# wrist.net
KiCad netlist of a schematic drawn in EAGLE
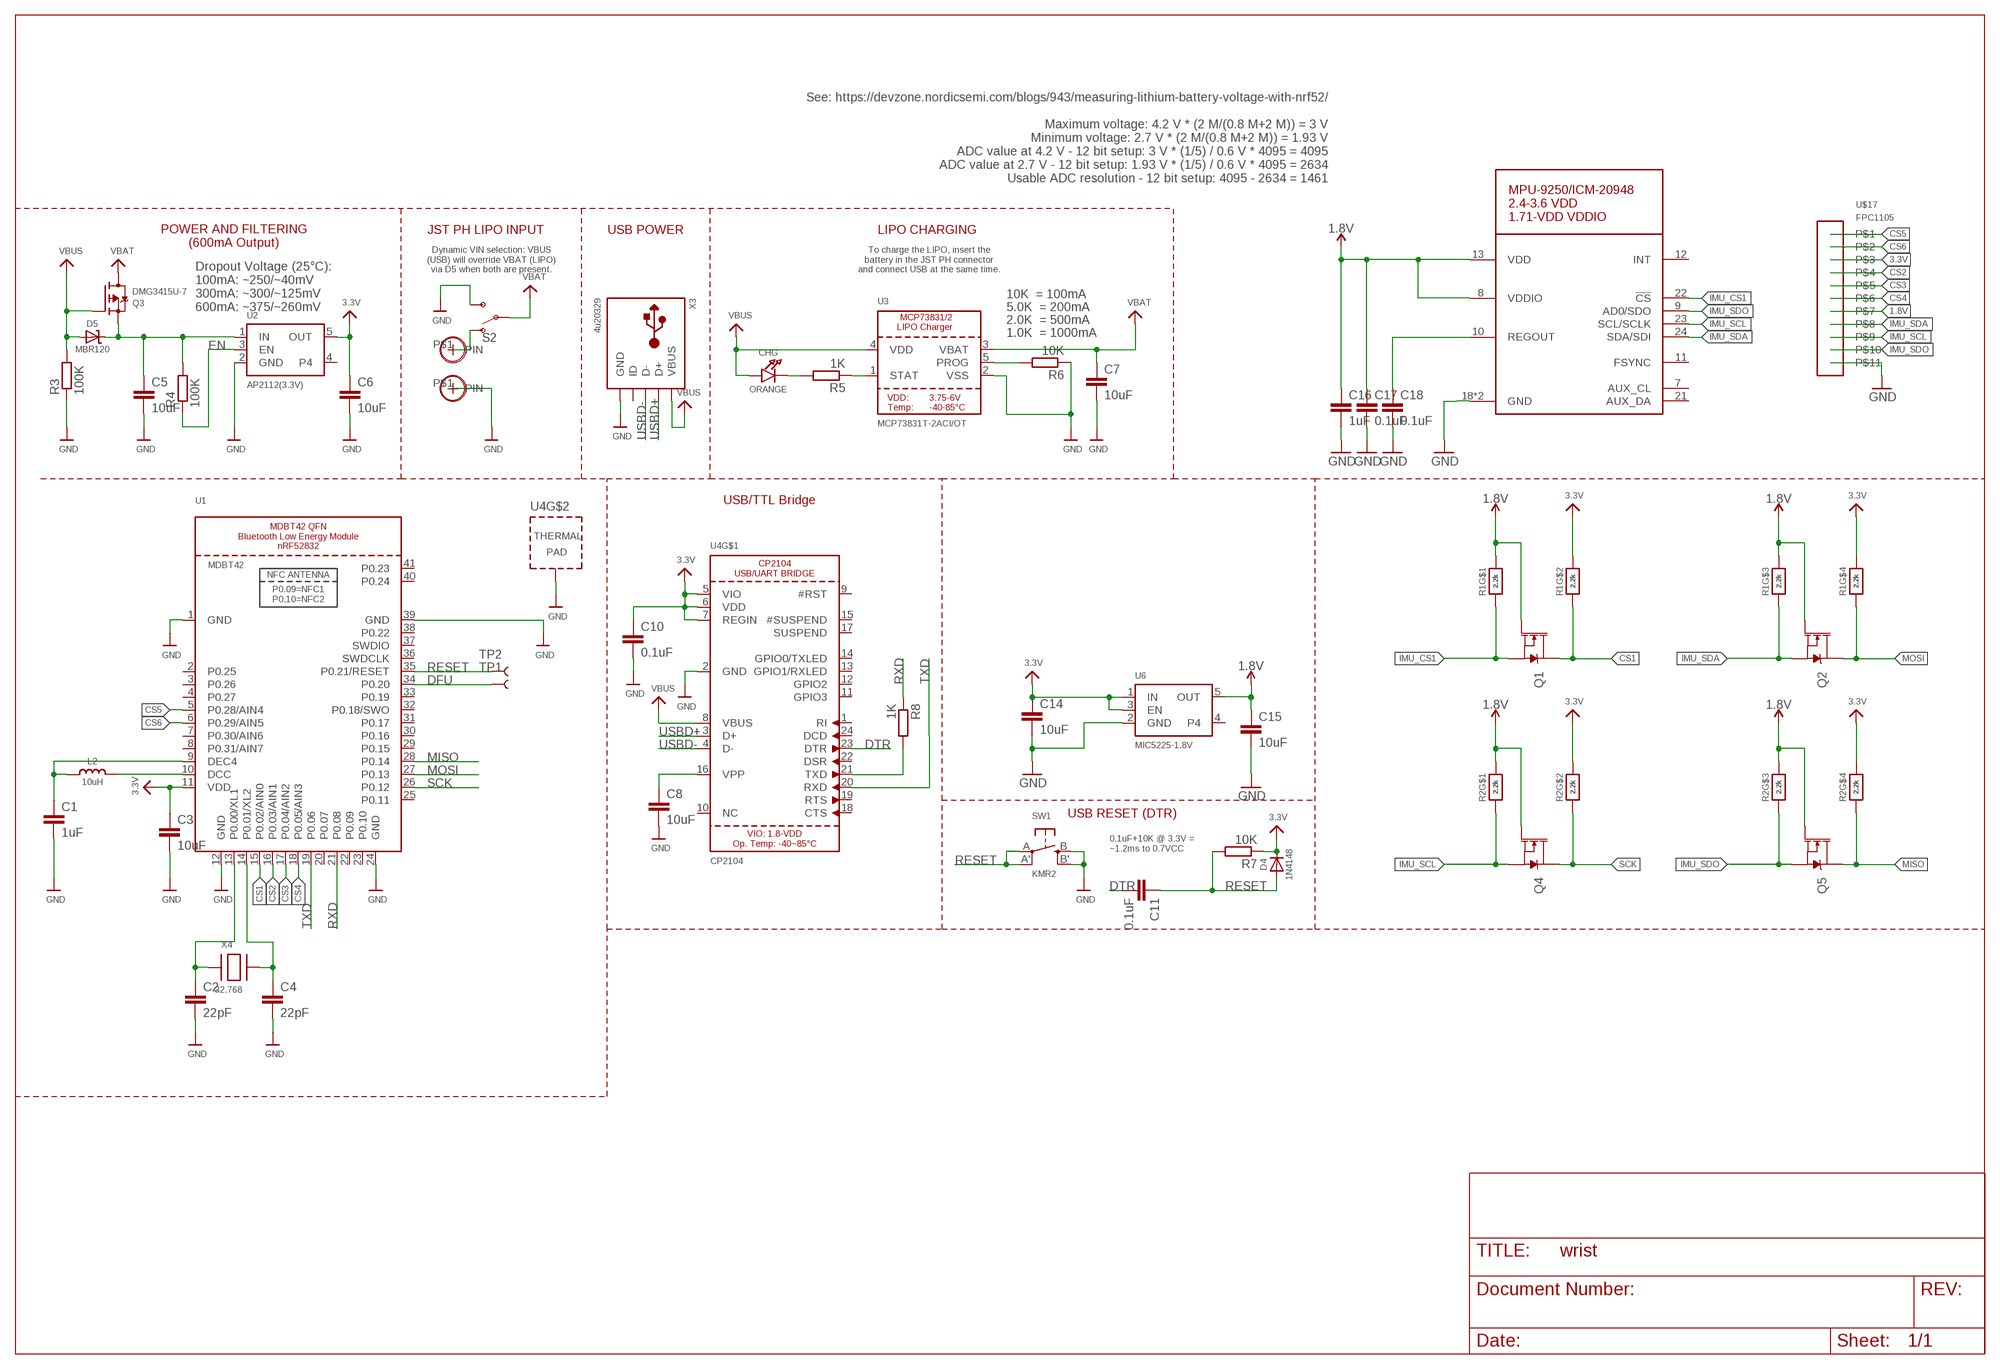
[diagram p0: schematic, sheet 1]

(export (version "E")
  (design (tool "Eeschema 10.0.6"))
  (components
    (comp (ref "C1")
      (value "1uF")
      (footprint "eagle-import:SPARKFUN-CAPACITORS_0402")
      (libsource (lib "eagle-import") (part "SPARKFUN-CAPACITORS_0.1UF-0402-16V-10%"))
    )
    (comp (ref "C2")
      (value "22pF")
      (footprint "eagle-import:SPARKFUN-CAPACITORS_0402")
      (libsource (lib "eagle-import") (part "SPARKFUN-CAPACITORS_0.1UF-0402-16V-10%"))
    )
    (comp (ref "C3")
      (value "10uF")
      (footprint "eagle-import:SPARKFUN-CAPACITORS_0402")
      (libsource (lib "eagle-import") (part "SPARKFUN-CAPACITORS_0.1UF-0402-16V-10%"))
    )
    (comp (ref "C4")
      (value "22pF")
      (footprint "eagle-import:SPARKFUN-CAPACITORS_0402")
      (libsource (lib "eagle-import") (part "SPARKFUN-CAPACITORS_0.1UF-0402-16V-10%"))
    )
    (comp (ref "C5")
      (value "10uF")
      (footprint "eagle-import:SPARKFUN-CAPACITORS_0402")
      (libsource (lib "eagle-import") (part "SPARKFUN-CAPACITORS_0.1UF-0402-16V-10%"))
    )
    (comp (ref "C6")
      (value "10uF")
      (footprint "eagle-import:SPARKFUN-CAPACITORS_0402")
      (libsource (lib "eagle-import") (part "SPARKFUN-CAPACITORS_0.1UF-0402-16V-10%"))
    )
    (comp (ref "C7")
      (value "10uF")
      (footprint "eagle-import:SPARKFUN-CAPACITORS_0402")
      (libsource (lib "eagle-import") (part "SPARKFUN-CAPACITORS_0.1UF-0402-16V-10%"))
    )
    (comp (ref "C8")
      (value "10uF")
      (footprint "eagle-import:SPARKFUN-CAPACITORS_0402")
      (libsource (lib "eagle-import") (part "SPARKFUN-CAPACITORS_0.1UF-0402-16V-10%"))
    )
    (comp (ref "C10")
      (value "0.1uF")
      (footprint "eagle-import:SPARKFUN-CAPACITORS_0402")
      (libsource (lib "eagle-import") (part "SPARKFUN-CAPACITORS_0.1UF-0402-16V-10%"))
    )
    (comp (ref "C11")
      (value "0.1uF")
      (footprint "eagle-import:SPARKFUN-CAPACITORS_0402")
      (libsource (lib "eagle-import") (part "SPARKFUN-CAPACITORS_0.1UF-0402-16V-10%"))
    )
    (comp (ref "C14")
      (value "10uF")
      (footprint "eagle-import:SPARKFUN-CAPACITORS_0402")
      (libsource (lib "eagle-import") (part "SPARKFUN-CAPACITORS_0.1UF-0402-16V-10%"))
    )
    (comp (ref "C15")
      (value "10uF")
      (footprint "eagle-import:SPARKFUN-CAPACITORS_0402")
      (libsource (lib "eagle-import") (part "SPARKFUN-CAPACITORS_0.1UF-0402-16V-10%"))
    )
    (comp (ref "C16")
      (value "1uF")
      (footprint "eagle-import:SPARKFUN-CAPACITORS_0402")
      (libsource (lib "eagle-import") (part "SPARKFUN-CAPACITORS_0.1UF-0402-16V-10%"))
    )
    (comp (ref "C17")
      (value "0.1uF")
      (footprint "eagle-import:SPARKFUN-CAPACITORS_0402")
      (libsource (lib "eagle-import") (part "SPARKFUN-CAPACITORS_0.1UF-0402-16V-10%"))
    )
    (comp (ref "C18")
      (value "0.1uF")
      (footprint "eagle-import:SPARKFUN-CAPACITORS_0402")
      (libsource (lib "eagle-import") (part "SPARKFUN-CAPACITORS_0.1UF-0402-16V-10%"))
    )
    (comp (ref "CHG")
      (value "ORANGE")
      (footprint "eagle-import:CHIPLED_0805_NOOUTLINE")
      (libsource (lib "eagle-import") (part "LED0805_NOOUTLINE"))
    )
    (comp (ref "D4")
      (value "1N4148")
      (footprint "eagle-import:SOD-323")
      (libsource (lib "eagle-import") (part "DIODESOD-323"))
    )
    (comp (ref "D5")
      (value "MBR120")
      (footprint "eagle-import:SOD-123")
      (libsource (lib "eagle-import") (part "DIODE-SCHOTTKYSOD-123"))
    )
    (comp (ref "IC1")
      (value "ADAFRUIT_SENSOR_MPU-9250_ICM20948")
      (footprint "eagle-import:ADAFRUIT_SENSOR_QFN24_3MM_NOEP")
      (libsource (lib "eagle-import") (part "ADAFRUIT_SENSOR_MPU-9250_ICM20948"))
    )
    (comp (ref "L2")
      (value "10uH")
      (footprint "eagle-import:0805-NO")
      (libsource (lib "eagle-import") (part "INDUCTOR0805-NO"))
    )
    (comp (ref "Q1")
      (value "20V/0.2A/8MHz/1.2Ω/1Vth")
      (footprint "eagle-import:SPARKFUN-DISCRETESEMI_SOT-416FL")
      (libsource (lib "eagle-import") (part "SPARKFUN-DISCRETESEMI_MOSFET-NCH-RE1C002UN"))
    )
    (comp (ref "Q2")
      (value "20V/0.2A/8MHz/1.2Ω/1Vth")
      (footprint "eagle-import:SPARKFUN-DISCRETESEMI_SOT-416FL")
      (libsource (lib "eagle-import") (part "SPARKFUN-DISCRETESEMI_MOSFET-NCH-RE1C002UN"))
    )
    (comp (ref "Q3")
      (value "DMG3415U-7")
      (footprint "eagle-import:SOT23-R")
      (libsource (lib "eagle-import") (part "MOSFET-P"))
    )
    (comp (ref "Q4")
      (value "20V/0.2A/8MHz/1.2Ω/1Vth")
      (footprint "eagle-import:SPARKFUN-DISCRETESEMI_SOT-416FL")
      (libsource (lib "eagle-import") (part "SPARKFUN-DISCRETESEMI_MOSFET-NCH-RE1C002UN"))
    )
    (comp (ref "Q5")
      (value "20V/0.2A/8MHz/1.2Ω/1Vth")
      (footprint "eagle-import:SPARKFUN-DISCRETESEMI_SOT-416FL")
      (libsource (lib "eagle-import") (part "SPARKFUN-DISCRETESEMI_MOSFET-NCH-RE1C002UN"))
    )
    (comp (ref "R1")
      (value "2.2k")
      (footprint "eagle-import:MICROBUILDER_RESPACK_4X0603")
      (libsource (lib "eagle-import") (part "MICROBUILDER_RESISTOR_4PACK"))
    )
    (comp (ref "R2")
      (value "2.2k")
      (footprint "eagle-import:MICROBUILDER_RESPACK_4X0603")
      (libsource (lib "eagle-import") (part "MICROBUILDER_RESISTOR_4PACK"))
    )
    (comp (ref "R3")
      (value "100K")
      (footprint "eagle-import:R0603")
      (libsource (lib "eagle-import") (part "R-EU_R0603"))
    )
    (comp (ref "R4")
      (value "100K")
      (footprint "eagle-import:R0603")
      (libsource (lib "eagle-import") (part "R-EU_R0603"))
    )
    (comp (ref "R5")
      (value "1K")
      (footprint "eagle-import:R0603")
      (libsource (lib "eagle-import") (part "R-EU_R0603"))
    )
    (comp (ref "R6")
      (value "10K")
      (footprint "eagle-import:R0603")
      (libsource (lib "eagle-import") (part "R-EU_R0603"))
    )
    (comp (ref "R7")
      (value "10K")
      (footprint "eagle-import:R0603")
      (libsource (lib "eagle-import") (part "R-EU_R0603"))
    )
    (comp (ref "R8")
      (value "1K")
      (footprint "eagle-import:R0603")
      (libsource (lib "eagle-import") (part "R-EU_R0603"))
    )
    (comp (ref "S2")
      (value "SWITCH-SPDT-SMD-RIGHT-ANGLE")
      (footprint "eagle-import:SWITCH_SPST_SMD_A")
      (libsource (lib "eagle-import") (part "SWITCH-SPDT-SMD-RIGHT-ANGLE"))
    )
    (comp (ref "SW1")
      (value "KMR2")
      (footprint "eagle-import:BTN_KMR2_4.6X2.8")
      (libsource (lib "eagle-import") (part "SWITCH_TACT_SMT4.6X2.8"))
    )
    (comp (ref "TP1")
      (value "TEST-POINT3")
      (footprint "eagle-import:PAD.03X.03")
      (libsource (lib "eagle-import") (part "TEST-POINT3"))
    )
    (comp (ref "TP2")
      (value "TEST-POINT3")
      (footprint "eagle-import:PAD.03X.03")
      (libsource (lib "eagle-import") (part "TEST-POINT3"))
    )
    (comp (ref "U$17")
      (value "FPC1105")
      (footprint "eagle-import:FPC1105")
      (libsource (lib "eagle-import") (part "FPC1105"))
    )
    (comp (ref "U$23")
      (value "M3-HOLE_M0.9-HOLE0.9MM")
      (footprint "eagle-import:M3-HOLE_M0.9-HOLE")
      (libsource (lib "eagle-import") (part "M3-HOLE_M0.9-HOLE0.9MM"))
    )
    (comp (ref "U$28")
      (value "M3-HOLE_M0.9-HOLE0.9MM")
      (footprint "eagle-import:M3-HOLE_M0.9-HOLE")
      (libsource (lib "eagle-import") (part "M3-HOLE_M0.9-HOLE0.9MM"))
    )
    (comp (ref "U1")
      (value "MDBT42")
      (footprint "eagle-import:BLE_MODULE_RAYTAC_MDBT42")
      (libsource (lib "eagle-import") (part "NRF52832_MODULE_MDBT42"))
    )
    (comp (ref "U2")
      (value "AP2112(3.3V)")
      (footprint "eagle-import:SOT23-5")
      (libsource (lib "eagle-import") (part "VREG_SOT23-5"))
    )
    (comp (ref "U3")
      (value "MCP73831T-2ACI/OT")
      (footprint "eagle-import:SOT23-5")
      (libsource (lib "eagle-import") (part "MCP73831/2"))
    )
    (comp (ref "U4")
      (value "CP2104")
      (footprint "eagle-import:QFN24_4MM_SMSC")
      (libsource (lib "eagle-import") (part "CP2104"))
    )
    (comp (ref "U6")
      (value "MIC5225-1.8V")
      (footprint "eagle-import:MICROBUILDER_SOT23-5")
      (libsource (lib "eagle-import") (part "MICROBUILDER_VREG_SOT23-5"))
    )
    (comp (ref "X3")
      (value "4u20329")
      (footprint "eagle-import:4UCONN_20329_V2")
      (libsource (lib "eagle-import") (part "USB_MICRO_20329_V2"))
    )
    (comp (ref "X4")
      (value "32.768")
      (footprint "eagle-import:XTAL3215")
      (libsource (lib "eagle-import") (part "XTAL-3.2X1.5"))
    )
  )
  (nets
    (net (code "1") (name "/DFU") (class "Default")
      (node (ref "TP1") (pin "P$1") (pinfunction "1_P$1") (pintype "bidirectional"))
      (node (ref "U1") (pin "34") (pinfunction "P0.20_34") (pintype "bidirectional"))
    )
    (net (code "2") (name "/DTR") (class "Default")
      (node (ref "C11") (pin "2") (pinfunction "2_2") (pintype "passive"))
      (node (ref "U4") (pin "23") (pinfunction "DTR_23") (pintype "output"))
    )
    (net (code "3") (name "/EN") (class "Default")
      (node (ref "R4") (pin "1") (pinfunction "1_1") (pintype "passive"))
      (node (ref "U2") (pin "3") (pinfunction "EN_3") (pintype "input"))
    )
    (net (code "4") (name "/RESET") (class "Default")
      (node (ref "C11") (pin "1") (pinfunction "1_1") (pintype "passive"))
      (node (ref "D4") (pin "A") (pinfunction "A_A") (pintype "passive"))
      (node (ref "R7") (pin "2") (pinfunction "2_2") (pintype "passive"))
      (node (ref "SW1") (pin "A") (pinfunction "P_A") (pintype "passive"))
      (node (ref "SW1") (pin "A'") (pinfunction "P1_A'") (pintype "passive"))
      (node (ref "TP2") (pin "P$1") (pinfunction "1_P$1") (pintype "bidirectional"))
      (node (ref "U1") (pin "35") (pinfunction "P0.21/RESET_35") (pintype "bidirectional"))
    )
    (net (code "5") (name "/RXD") (class "Default")
      (node (ref "R8") (pin "1") (pinfunction "1_1") (pintype "passive"))
      (node (ref "U1") (pin "21") (pinfunction "P0.08_21") (pintype "bidirectional"))
    )
    (net (code "6") (name "/TXD") (class "Default")
      (node (ref "U1") (pin "19") (pinfunction "P0.06_19") (pintype "bidirectional"))
      (node (ref "U4") (pin "20") (pinfunction "RXD_20") (pintype "input"))
    )
    (net (code "7") (name "/USBD+") (class "Default")
      (node (ref "U4") (pin "3") (pinfunction "D+_3") (pintype "bidirectional"))
      (node (ref "X3") (pin "D+") (pinfunction "D+_D+") (pintype "bidirectional"))
    )
    (net (code "8") (name "/USBD-") (class "Default")
      (node (ref "U4") (pin "4") (pinfunction "D-_4") (pintype "bidirectional"))
      (node (ref "X3") (pin "D-") (pinfunction "D-_D-") (pintype "bidirectional"))
    )
    (net (code "9") (name "1.8V") (class "Default")
      (node (ref "C15") (pin "1") (pinfunction "1_1") (pintype "passive"))
      (node (ref "C16") (pin "1") (pinfunction "1_1") (pintype "passive"))
      (node (ref "C17") (pin "1") (pinfunction "1_1") (pintype "passive"))
      (node (ref "IC1") (pin "13") (pinfunction "VDD_13") (pintype "bidirectional"))
      (node (ref "IC1") (pin "8") (pinfunction "VDDIO_8") (pintype "bidirectional"))
      (node (ref "Q1") (pin "1") (pinfunction "G_1") (pintype "bidirectional"))
      (node (ref "Q2") (pin "1") (pinfunction "G_1") (pintype "bidirectional"))
      (node (ref "Q4") (pin "1") (pinfunction "G_1") (pintype "bidirectional"))
      (node (ref "Q5") (pin "1") (pinfunction "G_1") (pintype "bidirectional"))
      (node (ref "R1") (pin "6") (pinfunction "2_6") (pintype "passive"))
      (node (ref "R1") (pin "8") (pinfunction "2_8") (pintype "passive"))
      (node (ref "R2") (pin "6") (pinfunction "2_6") (pintype "passive"))
      (node (ref "R2") (pin "8") (pinfunction "2_8") (pintype "passive"))
      (node (ref "U$17") (pin "P$7") (pinfunction "P$7_P$7") (pintype "bidirectional"))
      (node (ref "U6") (pin "5") (pinfunction "OUT_5") (pintype "power_in"))
    )
    (net (code "10") (name "3.3V") (class "Default")
      (node (ref "C10") (pin "1") (pinfunction "1_1") (pintype "passive"))
      (node (ref "C14") (pin "1") (pinfunction "1_1") (pintype "passive"))
      (node (ref "C3") (pin "1") (pinfunction "1_1") (pintype "passive"))
      (node (ref "C6") (pin "1") (pinfunction "1_1") (pintype "passive"))
      (node (ref "D4") (pin "C") (pinfunction "C_C") (pintype "passive"))
      (node (ref "R1") (pin "5") (pinfunction "2_5") (pintype "passive"))
      (node (ref "R1") (pin "7") (pinfunction "2_7") (pintype "passive"))
      (node (ref "R2") (pin "5") (pinfunction "2_5") (pintype "passive"))
      (node (ref "R2") (pin "7") (pinfunction "2_7") (pintype "passive"))
      (node (ref "R7") (pin "1") (pinfunction "1_1") (pintype "passive"))
      (node (ref "U$17") (pin "P$3") (pinfunction "P$3_P$3") (pintype "bidirectional"))
      (node (ref "U1") (pin "11") (pinfunction "VDD_11") (pintype "bidirectional"))
      (node (ref "U2") (pin "5") (pinfunction "OUT_5") (pintype "power_in"))
      (node (ref "U4") (pin "5") (pinfunction "VIO_5") (pintype "power_in"))
      (node (ref "U4") (pin "6") (pinfunction "VDD_6") (pintype "power_in"))
      (node (ref "U4") (pin "7") (pinfunction "REGIN_7") (pintype "power_in"))
      (node (ref "U6") (pin "1") (pinfunction "IN_1") (pintype "power_in"))
      (node (ref "U6") (pin "3") (pinfunction "EN_3") (pintype "input"))
    )
    (net (code "11") (name "CS1") (class "Default")
      (node (ref "Q1") (pin "3") (pinfunction "D_3") (pintype "bidirectional"))
      (node (ref "R1") (pin "2") (pinfunction "1_2") (pintype "passive"))
      (node (ref "U1") (pin "15") (pinfunction "P0.02/AIN0_15") (pintype "bidirectional"))
    )
    (net (code "12") (name "CS2") (class "Default")
      (node (ref "U$17") (pin "P$4") (pinfunction "P$4_P$4") (pintype "bidirectional"))
      (node (ref "U1") (pin "16") (pinfunction "P0.03/AIN1_16") (pintype "bidirectional"))
    )
    (net (code "13") (name "CS3") (class "Default")
      (node (ref "U$17") (pin "P$5") (pinfunction "P$5_P$5") (pintype "bidirectional"))
      (node (ref "U1") (pin "17") (pinfunction "P0.04/AIN2_17") (pintype "bidirectional"))
    )
    (net (code "14") (name "CS4") (class "Default")
      (node (ref "U$17") (pin "P$6") (pinfunction "P$6_P$6") (pintype "bidirectional"))
      (node (ref "U1") (pin "18") (pinfunction "P0.05/AIN3_18") (pintype "bidirectional"))
    )
    (net (code "15") (name "CS5") (class "Default")
      (node (ref "U$17") (pin "P$1") (pinfunction "P$1_P$1") (pintype "bidirectional"))
      (node (ref "U1") (pin "5") (pinfunction "P0.28/AIN4_5") (pintype "bidirectional"))
    )
    (net (code "16") (name "CS6") (class "Default")
      (node (ref "U$17") (pin "P$2") (pinfunction "P$2_P$2") (pintype "bidirectional"))
      (node (ref "U1") (pin "6") (pinfunction "P0.29/AIN5_6") (pintype "bidirectional"))
    )
    (net (code "17") (name "GND") (class "Default")
      (node (ref "C1") (pin "2") (pinfunction "2_2") (pintype "passive"))
      (node (ref "C10") (pin "2") (pinfunction "2_2") (pintype "passive"))
      (node (ref "C14") (pin "2") (pinfunction "2_2") (pintype "passive"))
      (node (ref "C15") (pin "2") (pinfunction "2_2") (pintype "passive"))
      (node (ref "C16") (pin "2") (pinfunction "2_2") (pintype "passive"))
      (node (ref "C17") (pin "2") (pinfunction "2_2") (pintype "passive"))
      (node (ref "C18") (pin "2") (pinfunction "2_2") (pintype "passive"))
      (node (ref "C2") (pin "2") (pinfunction "2_2") (pintype "passive"))
      (node (ref "C3") (pin "2") (pinfunction "2_2") (pintype "passive"))
      (node (ref "C4") (pin "2") (pinfunction "2_2") (pintype "passive"))
      (node (ref "C5") (pin "2") (pinfunction "2_2") (pintype "passive"))
      (node (ref "C6") (pin "2") (pinfunction "2_2") (pintype "passive"))
      (node (ref "C7") (pin "2") (pinfunction "2_2") (pintype "passive"))
      (node (ref "C8") (pin "2") (pinfunction "2_2") (pintype "passive"))
      (node (ref "IC1") (pin "18") (pinfunction "GND_18") (pintype "bidirectional"))
      (node (ref "IC1") (pin "20") (pinfunction "GND_20") (pintype "bidirectional"))
      (node (ref "R3") (pin "1") (pinfunction "1_1") (pintype "passive"))
      (node (ref "R6") (pin "1") (pinfunction "1_1") (pintype "passive"))
      (node (ref "S2") (pin "3") (pinfunction "S_3") (pintype "passive"))
      (node (ref "SW1") (pin "B") (pinfunction "S_B") (pintype "passive"))
      (node (ref "SW1") (pin "B'") (pinfunction "S1_B'") (pintype "passive"))
      (node (ref "U$17") (pin "P$11") (pinfunction "P$11_P$11") (pintype "bidirectional"))
      (node (ref "U$28") (pin "P$1") (pinfunction "PIN_P$1") (pintype "bidirectional"))
      (node (ref "U1") (pin "1") (pinfunction "GND_1") (pintype "bidirectional"))
      (node (ref "U1") (pin "12") (pinfunction "GND_12") (pintype "bidirectional"))
      (node (ref "U1") (pin "24") (pinfunction "GND_24") (pintype "bidirectional"))
      (node (ref "U1") (pin "39") (pinfunction "GND_39") (pintype "bidirectional"))
      (node (ref "U2") (pin "2") (pinfunction "GND_2") (pintype "power_in"))
      (node (ref "U3") (pin "2") (pinfunction "VSS_2") (pintype "power_in"))
      (node (ref "U4") (pin "2") (pinfunction "GND_2") (pintype "power_in"))
      (node (ref "U4") (pin "THERM") (pinfunction "TP_THERM") (pintype "power_in"))
      (node (ref "U6") (pin "2") (pinfunction "GND_2") (pintype "power_in"))
      (node (ref "X3") (pin "BASE@1") (pinfunction "GND_BASE@1") (pintype "power_in"))
      (node (ref "X3") (pin "BASE@2") (pinfunction "GND_BASE@2") (pintype "power_in"))
      (node (ref "X3") (pin "GND") (pinfunction "GND_GND") (pintype "power_in"))
      (node (ref "X3") (pin "SPRT@1") (pinfunction "GND_SPRT@1") (pintype "power_in"))
      (node (ref "X3") (pin "SPRT@2") (pinfunction "GND_SPRT@2") (pintype "power_in"))
      (node (ref "X3") (pin "SPRT@3") (pinfunction "GND_SPRT@3") (pintype "power_in"))
      (node (ref "X3") (pin "SPRT@4") (pinfunction "GND_SPRT@4") (pintype "power_in"))
    )
    (net (code "18") (name "IMU_CS1") (class "Default")
      (node (ref "IC1") (pin "22") (pinfunction "~{CS}_22") (pintype "bidirectional"))
      (node (ref "Q1") (pin "2") (pinfunction "S_2") (pintype "bidirectional"))
      (node (ref "R1") (pin "1") (pinfunction "1_1") (pintype "passive"))
    )
    (net (code "19") (name "IMU_SCL") (class "Default")
      (node (ref "IC1") (pin "23") (pinfunction "SCL/SCLK_23") (pintype "bidirectional"))
      (node (ref "Q4") (pin "2") (pinfunction "S_2") (pintype "bidirectional"))
      (node (ref "R2") (pin "1") (pinfunction "1_1") (pintype "passive"))
      (node (ref "U$17") (pin "P$9") (pinfunction "P$9_P$9") (pintype "bidirectional"))
    )
    (net (code "20") (name "IMU_SDA") (class "Default")
      (node (ref "IC1") (pin "24") (pinfunction "SDA/SDI_24") (pintype "bidirectional"))
      (node (ref "Q2") (pin "2") (pinfunction "S_2") (pintype "bidirectional"))
      (node (ref "R1") (pin "3") (pinfunction "1_3") (pintype "passive"))
      (node (ref "U$17") (pin "P$8") (pinfunction "P$8_P$8") (pintype "bidirectional"))
    )
    (net (code "21") (name "IMU_SDO") (class "Default")
      (node (ref "IC1") (pin "9") (pinfunction "AD0/SDO_9") (pintype "bidirectional"))
      (node (ref "Q5") (pin "2") (pinfunction "S_2") (pintype "bidirectional"))
      (node (ref "R2") (pin "3") (pinfunction "1_3") (pintype "passive"))
      (node (ref "U$17") (pin "P$10") (pinfunction "P$10_P$10") (pintype "bidirectional"))
    )
    (net (code "22") (name "MISO") (class "Default")
      (node (ref "Q5") (pin "3") (pinfunction "D_3") (pintype "bidirectional"))
      (node (ref "R2") (pin "4") (pinfunction "1_4") (pintype "passive"))
      (node (ref "U1") (pin "28") (pinfunction "P0.14_28") (pintype "bidirectional"))
    )
    (net (code "23") (name "MOSI") (class "Default")
      (node (ref "Q2") (pin "3") (pinfunction "D_3") (pintype "bidirectional"))
      (node (ref "R1") (pin "4") (pinfunction "1_4") (pintype "passive"))
      (node (ref "U1") (pin "27") (pinfunction "P0.13_27") (pintype "bidirectional"))
    )
    (net (code "24") (name "Net-(CHG-PadC)") (class "Default")
      (node (ref "CHG") (pin "C") (pinfunction "C_C") (pintype "passive"))
      (node (ref "R5") (pin "2") (pinfunction "2_2") (pintype "passive"))
    )
    (net (code "25") (name "Net-(IC1-REGOUT)") (class "Default")
      (node (ref "C18") (pin "1") (pinfunction "1_1") (pintype "passive"))
      (node (ref "IC1") (pin "10") (pinfunction "REGOUT_10") (pintype "bidirectional"))
    )
    (net (code "26") (name "Net-(Q3-S)") (class "Default")
      (node (ref "C5") (pin "1") (pinfunction "1_1") (pintype "passive"))
      (node (ref "D5") (pin "C") (pinfunction "C_C") (pintype "passive"))
      (node (ref "Q3") (pin "2") (pinfunction "S_2") (pintype "passive"))
      (node (ref "R4") (pin "2") (pinfunction "2_2") (pintype "passive"))
      (node (ref "U2") (pin "1") (pinfunction "IN_1") (pintype "power_in"))
    )
    (net (code "27") (name "Net-(S2-O)") (class "Default")
      (node (ref "S2") (pin "1") (pinfunction "O_1") (pintype "passive"))
      (node (ref "U$23") (pin "P$1") (pinfunction "PIN_P$1") (pintype "bidirectional"))
    )
    (net (code "28") (name "Net-(U1-DCC)") (class "Default")
      (node (ref "L2") (pin "2") (pinfunction "2_2") (pintype "passive"))
      (node (ref "U1") (pin "10") (pinfunction "DCC_10") (pintype "bidirectional"))
    )
    (net (code "29") (name "Net-(U1-DEC4)") (class "Default")
      (node (ref "C1") (pin "1") (pinfunction "1_1") (pintype "passive"))
      (node (ref "L2") (pin "1") (pinfunction "1_1") (pintype "passive"))
      (node (ref "U1") (pin "9") (pinfunction "DEC4_9") (pintype "bidirectional"))
    )
    (net (code "30") (name "Net-(U1-P0.00{slash}XL1)") (class "Default")
      (node (ref "C2") (pin "1") (pinfunction "1_1") (pintype "passive"))
      (node (ref "U1") (pin "13") (pinfunction "P0.00/XL1_13") (pintype "bidirectional"))
      (node (ref "X4") (pin "P$1") (pinfunction "P$1_P$1") (pintype "bidirectional"))
    )
    (net (code "31") (name "Net-(U1-P0.01{slash}XL2)") (class "Default")
      (node (ref "C4") (pin "1") (pinfunction "1_1") (pintype "passive"))
      (node (ref "U1") (pin "14") (pinfunction "P0.01/XL2_14") (pintype "bidirectional"))
      (node (ref "X4") (pin "P$2") (pinfunction "P$2_P$2") (pintype "bidirectional"))
    )
    (net (code "32") (name "Net-(U3-PROG)") (class "Default")
      (node (ref "R6") (pin "2") (pinfunction "2_2") (pintype "passive"))
      (node (ref "U3") (pin "5") (pinfunction "PROG_5") (pintype "input"))
    )
    (net (code "33") (name "Net-(U3-STAT)") (class "Default")
      (node (ref "R5") (pin "1") (pinfunction "1_1") (pintype "passive"))
      (node (ref "U3") (pin "1") (pinfunction "STAT_1") (pintype "output"))
    )
    (net (code "34") (name "Net-(U4A-TXD)") (class "Default")
      (node (ref "R8") (pin "2") (pinfunction "2_2") (pintype "passive"))
      (node (ref "U4") (pin "21") (pinfunction "TXD_21") (pintype "output"))
    )
    (net (code "35") (name "Net-(U4A-VPP)") (class "Default")
      (node (ref "C8") (pin "1") (pinfunction "1_1") (pintype "passive"))
      (node (ref "U4") (pin "16") (pinfunction "VPP_16") (pintype "bidirectional"))
    )
    (net (code "36") (name "SCK") (class "Default")
      (node (ref "Q4") (pin "3") (pinfunction "D_3") (pintype "bidirectional"))
      (node (ref "R2") (pin "2") (pinfunction "1_2") (pintype "passive"))
      (node (ref "U1") (pin "26") (pinfunction "P0.12_26") (pintype "bidirectional"))
    )
    (net (code "37") (name "VBAT") (class "Default")
      (node (ref "C7") (pin "1") (pinfunction "1_1") (pintype "passive"))
      (node (ref "Q3") (pin "3") (pinfunction "D_3") (pintype "passive"))
      (node (ref "S2") (pin "2") (pinfunction "P_2") (pintype "passive"))
      (node (ref "U3") (pin "3") (pinfunction "VBAT_3") (pintype "power_in"))
    )
    (net (code "38") (name "VBUS") (class "Default")
      (node (ref "CHG") (pin "A") (pinfunction "A_A") (pintype "passive"))
      (node (ref "D5") (pin "A") (pinfunction "A_A") (pintype "passive"))
      (node (ref "Q3") (pin "1") (pinfunction "G_1") (pintype "passive"))
      (node (ref "R3") (pin "2") (pinfunction "2_2") (pintype "passive"))
      (node (ref "U3") (pin "4") (pinfunction "VDD_4") (pintype "power_in"))
      (node (ref "U4") (pin "8") (pinfunction "VBUS_8") (pintype "power_in"))
      (node (ref "X3") (pin "VBUS") (pinfunction "VBUS_VBUS") (pintype "power_in"))
    )
    (net (code "39") (name "unconnected-(IC1-AUX_CL-Pad7)") (class "Default")
      (node (ref "IC1") (pin "7") (pinfunction "AUX_CL_7") (pintype "bidirectional"))
    )
    (net (code "40") (name "unconnected-(IC1-AUX_DA-Pad21)") (class "Default")
      (node (ref "IC1") (pin "21") (pinfunction "AUX_DA_21") (pintype "bidirectional"))
    )
    (net (code "41") (name "unconnected-(IC1-FSYNC-Pad11)") (class "Default")
      (node (ref "IC1") (pin "11") (pinfunction "FSYNC_11") (pintype "bidirectional"))
    )
    (net (code "42") (name "unconnected-(IC1-INT-Pad12)") (class "Default")
      (node (ref "IC1") (pin "12") (pinfunction "INT_12") (pintype "bidirectional"))
    )
    (net (code "43") (name "unconnected-(U1-P0.07-Pad20)") (class "Default")
      (node (ref "U1") (pin "20") (pinfunction "P0.07_20") (pintype "bidirectional"))
    )
    (net (code "44") (name "unconnected-(U1-P0.09-Pad22)") (class "Default")
      (node (ref "U1") (pin "22") (pinfunction "P0.09_22") (pintype "bidirectional"))
    )
    (net (code "45") (name "unconnected-(U1-P0.10-Pad23)") (class "Default")
      (node (ref "U1") (pin "23") (pinfunction "P0.10_23") (pintype "bidirectional"))
    )
    (net (code "46") (name "unconnected-(U1-P0.11-Pad25)") (class "Default")
      (node (ref "U1") (pin "25") (pinfunction "P0.11_25") (pintype "bidirectional"))
    )
    (net (code "47") (name "unconnected-(U1-P0.15-Pad29)") (class "Default")
      (node (ref "U1") (pin "29") (pinfunction "P0.15_29") (pintype "bidirectional"))
    )
    (net (code "48") (name "unconnected-(U1-P0.16-Pad30)") (class "Default")
      (node (ref "U1") (pin "30") (pinfunction "P0.16_30") (pintype "bidirectional"))
    )
    (net (code "49") (name "unconnected-(U1-P0.17-Pad31)") (class "Default")
      (node (ref "U1") (pin "31") (pinfunction "P0.17_31") (pintype "bidirectional"))
    )
    (net (code "50") (name "unconnected-(U1-P0.18{slash}SWO-Pad32)") (class "Default")
      (node (ref "U1") (pin "32") (pinfunction "P0.18/SWO_32") (pintype "bidirectional"))
    )
    (net (code "51") (name "unconnected-(U1-P0.19-Pad33)") (class "Default")
      (node (ref "U1") (pin "33") (pinfunction "P0.19_33") (pintype "bidirectional"))
    )
    (net (code "52") (name "unconnected-(U1-P0.22-Pad38)") (class "Default")
      (node (ref "U1") (pin "38") (pinfunction "P0.22_38") (pintype "bidirectional"))
    )
    (net (code "53") (name "unconnected-(U1-P0.23-Pad41)") (class "Default")
      (node (ref "U1") (pin "41") (pinfunction "P0.23_41") (pintype "bidirectional"))
    )
    (net (code "54") (name "unconnected-(U1-P0.24-Pad40)") (class "Default")
      (node (ref "U1") (pin "40") (pinfunction "P0.24_40") (pintype "bidirectional"))
    )
    (net (code "55") (name "unconnected-(U1-P0.25-Pad2)") (class "Default")
      (node (ref "U1") (pin "2") (pinfunction "P0.25_2") (pintype "bidirectional"))
    )
    (net (code "56") (name "unconnected-(U1-P0.26-Pad3)") (class "Default")
      (node (ref "U1") (pin "3") (pinfunction "P0.26_3") (pintype "bidirectional"))
    )
    (net (code "57") (name "unconnected-(U1-P0.27-Pad4)") (class "Default")
      (node (ref "U1") (pin "4") (pinfunction "P0.27_4") (pintype "bidirectional"))
    )
    (net (code "58") (name "unconnected-(U1-P0.30{slash}AIN6-Pad7)") (class "Default")
      (node (ref "U1") (pin "7") (pinfunction "P0.30/AIN6_7") (pintype "bidirectional"))
    )
    (net (code "59") (name "unconnected-(U1-P0.31{slash}AIN7-Pad8)") (class "Default")
      (node (ref "U1") (pin "8") (pinfunction "P0.31/AIN7_8") (pintype "bidirectional"))
    )
    (net (code "60") (name "unconnected-(U1-SWDCLK-Pad36)") (class "Default")
      (node (ref "U1") (pin "36") (pinfunction "SWDCLK_36") (pintype "bidirectional"))
    )
    (net (code "61") (name "unconnected-(U1-SWDIO-Pad37)") (class "Default")
      (node (ref "U1") (pin "37") (pinfunction "SWDIO_37") (pintype "bidirectional"))
    )
    (net (code "62") (name "unconnected-(U2-P4-Pad4)") (class "Default")
      (node (ref "U2") (pin "4") (pinfunction "P4_4") (pintype "bidirectional"))
    )
    (net (code "63") (name "unconnected-(U4A-#RST-Pad9)") (class "Default")
      (node (ref "U4") (pin "9") (pinfunction "#RST_9") (pintype "bidirectional"))
    )
    (net (code "64") (name "unconnected-(U4A-#SUSPEND-Pad15)") (class "Default")
      (node (ref "U4") (pin "15") (pinfunction "#SUSPEND_15") (pintype "output"))
    )
    (net (code "65") (name "unconnected-(U4A-CTS-Pad18)") (class "Default")
      (node (ref "U4") (pin "18") (pinfunction "CTS_18") (pintype "input"))
    )
    (net (code "66") (name "unconnected-(U4A-DCD-Pad24)") (class "Default")
      (node (ref "U4") (pin "24") (pinfunction "DCD_24") (pintype "input"))
    )
    (net (code "67") (name "unconnected-(U4A-DSR-Pad22)") (class "Default")
      (node (ref "U4") (pin "22") (pinfunction "DSR_22") (pintype "input"))
    )
    (net (code "68") (name "unconnected-(U4A-GPIO0{slash}TXLED-Pad14)") (class "Default")
      (node (ref "U4") (pin "14") (pinfunction "GPIO0/TXLED_14") (pintype "bidirectional"))
    )
    (net (code "69") (name "unconnected-(U4A-GPIO1{slash}RXLED-Pad13)") (class "Default")
      (node (ref "U4") (pin "13") (pinfunction "GPIO1/RXLED_13") (pintype "bidirectional"))
    )
    (net (code "70") (name "unconnected-(U4A-GPIO2-Pad12)") (class "Default")
      (node (ref "U4") (pin "12") (pinfunction "GPIO2_12") (pintype "bidirectional"))
    )
    (net (code "71") (name "unconnected-(U4A-GPIO3-Pad11)") (class "Default")
      (node (ref "U4") (pin "11") (pinfunction "GPIO3_11") (pintype "bidirectional"))
    )
    (net (code "72") (name "unconnected-(U4A-NC-Pad10)") (class "Default")
      (node (ref "U4") (pin "10") (pinfunction "NC_10") (pintype "no_connect"))
    )
    (net (code "73") (name "unconnected-(U4A-RI-Pad1)") (class "Default")
      (node (ref "U4") (pin "1") (pinfunction "RI_1") (pintype "input"))
    )
    (net (code "74") (name "unconnected-(U4A-RTS-Pad19)") (class "Default")
      (node (ref "U4") (pin "19") (pinfunction "RTS_19") (pintype "output"))
    )
    (net (code "75") (name "unconnected-(U4A-SUSPEND-Pad17)") (class "Default")
      (node (ref "U4") (pin "17") (pinfunction "SUSPEND_17") (pintype "output"))
    )
    (net (code "76") (name "unconnected-(U6-P4-Pad4)") (class "Default")
      (node (ref "U6") (pin "4") (pinfunction "P4_4") (pintype "bidirectional"))
    )
    (net (code "77") (name "unconnected-(X3-PadID)") (class "Default")
      (node (ref "X3") (pin "ID") (pinfunction "ID_ID") (pintype "bidirectional"))
    )
  )
)
